# 8-Bit_Adder.net
KiCad netlist of a schematic drawn in EAGLE
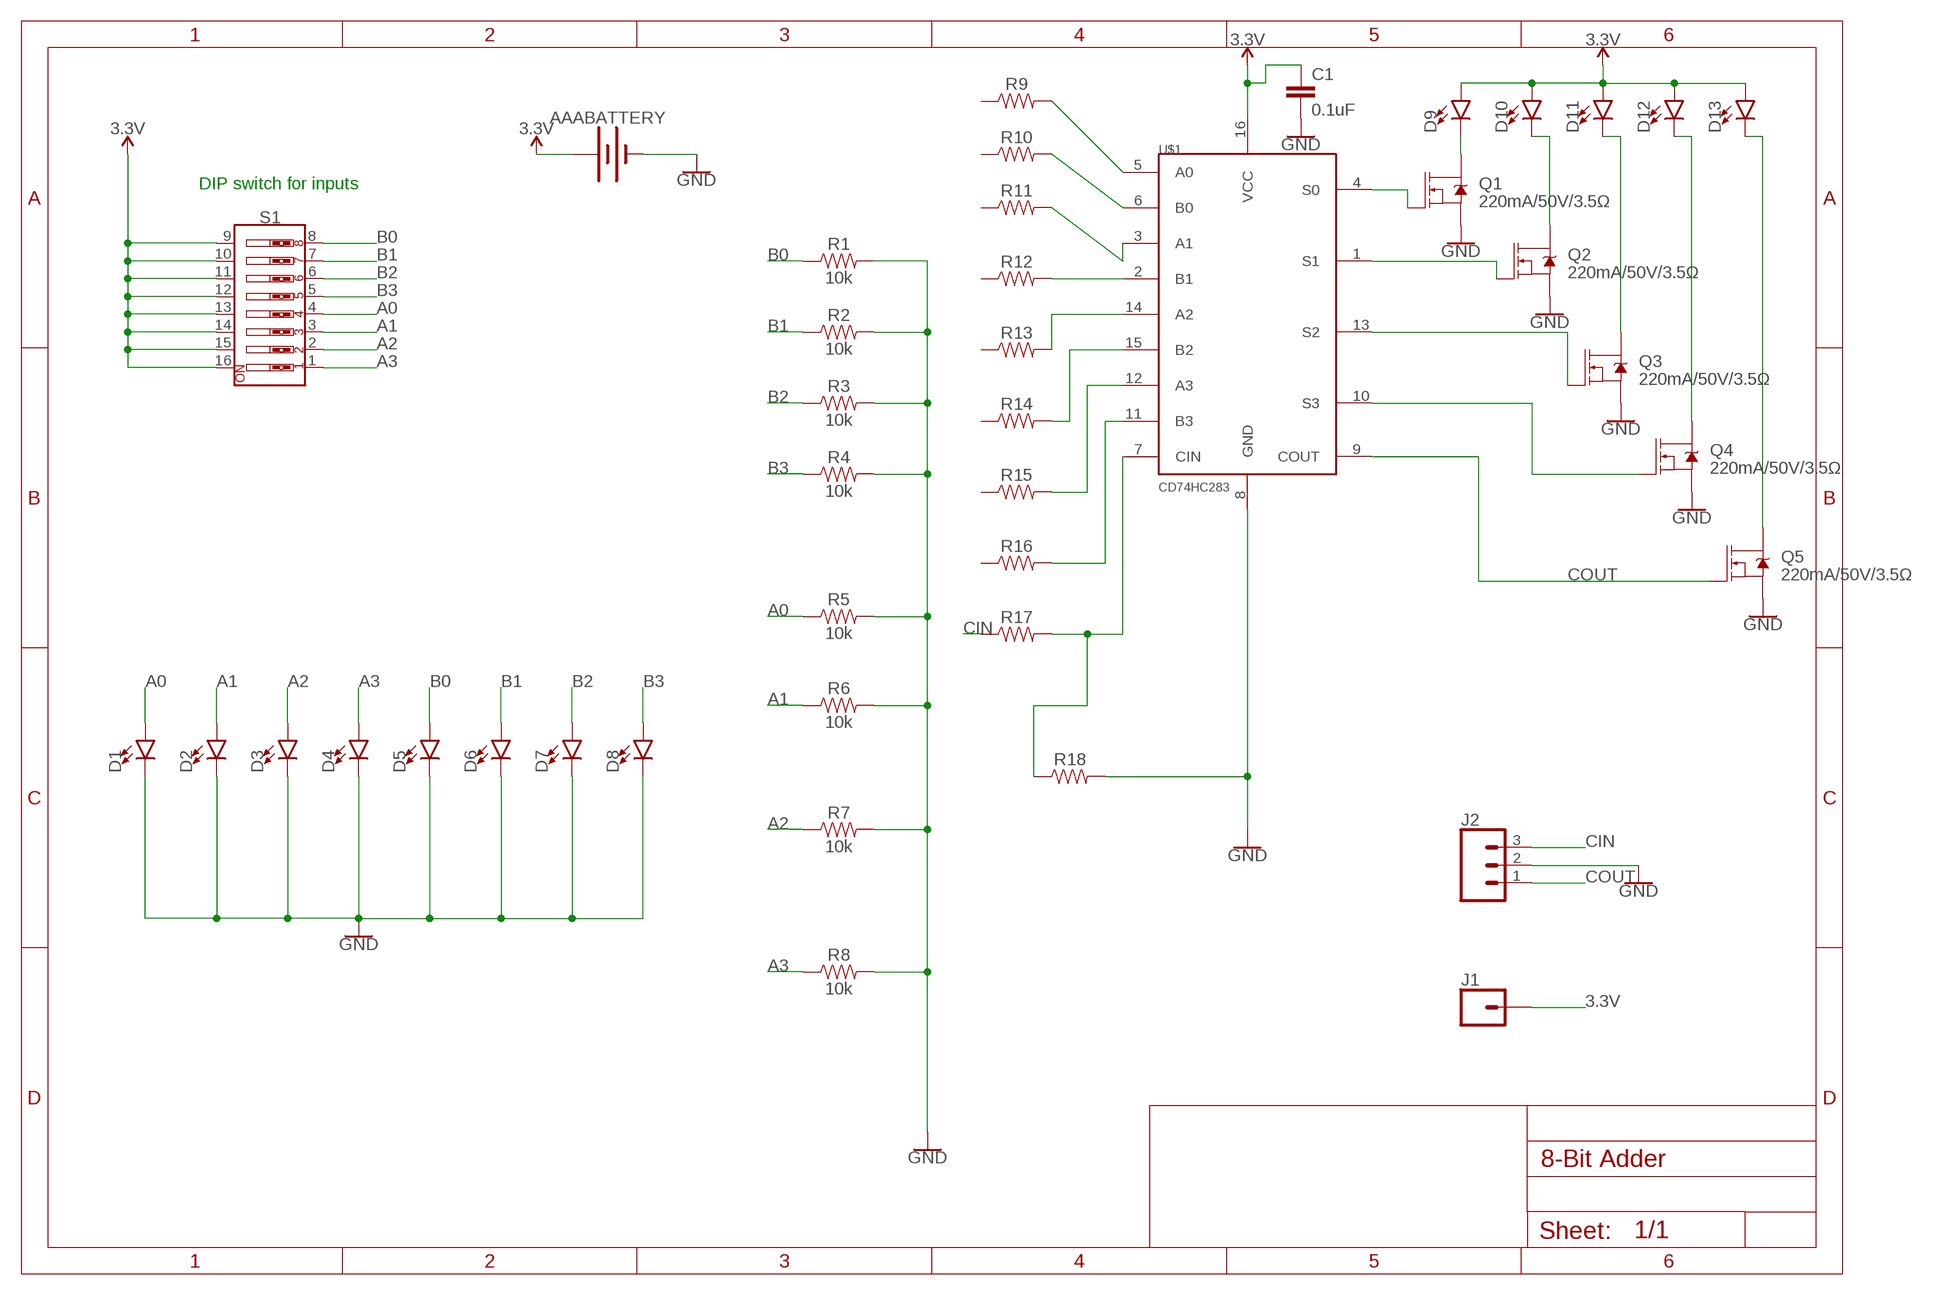
[diagram p0: schematic, sheet 1]

(export (version "E")
  (design (tool "Eeschema 10.0.6"))
  (components
    (comp (ref "AAABATTERY")
      (value "BATTERY-AAA")
      (footprint "eagle-import:BATTERY-AAA")
      (libsource (lib "eagle-import") (part "BATTERY-AAA"))
    )
    (comp (ref "C1")
      (value "0.1uF")
      (footprint "eagle-import:0603")
      (libsource (lib "eagle-import") (part "0.1UF-0603-25V-(+80/-20%)"))
    )
    (comp (ref "D1")
      (value "LED5MM")
      (footprint "eagle-import:LED_5MM")
      (libsource (lib "eagle-import") (part "LED5MM"))
    )
    (comp (ref "D2")
      (value "LED5MM")
      (footprint "eagle-import:LED_5MM")
      (libsource (lib "eagle-import") (part "LED5MM"))
    )
    (comp (ref "D3")
      (value "LED5MM")
      (footprint "eagle-import:LED_5MM")
      (libsource (lib "eagle-import") (part "LED5MM"))
    )
    (comp (ref "D4")
      (value "LED5MM")
      (footprint "eagle-import:LED_5MM")
      (libsource (lib "eagle-import") (part "LED5MM"))
    )
    (comp (ref "D5")
      (value "LED5MM")
      (footprint "eagle-import:LED_5MM")
      (libsource (lib "eagle-import") (part "LED5MM"))
    )
    (comp (ref "D6")
      (value "LED5MM")
      (footprint "eagle-import:LED_5MM")
      (libsource (lib "eagle-import") (part "LED5MM"))
    )
    (comp (ref "D7")
      (value "LED5MM")
      (footprint "eagle-import:LED_5MM")
      (libsource (lib "eagle-import") (part "LED5MM"))
    )
    (comp (ref "D8")
      (value "LED5MM")
      (footprint "eagle-import:LED_5MM")
      (libsource (lib "eagle-import") (part "LED5MM"))
    )
    (comp (ref "D9")
      (value "LED5MM")
      (footprint "eagle-import:LED_5MM")
      (libsource (lib "eagle-import") (part "LED5MM"))
    )
    (comp (ref "D10")
      (value "LED5MM")
      (footprint "eagle-import:LED_5MM")
      (libsource (lib "eagle-import") (part "LED5MM"))
    )
    (comp (ref "D11")
      (value "LED5MM")
      (footprint "eagle-import:LED_5MM")
      (libsource (lib "eagle-import") (part "LED5MM"))
    )
    (comp (ref "D12")
      (value "LED5MM")
      (footprint "eagle-import:LED_5MM")
      (libsource (lib "eagle-import") (part "LED5MM"))
    )
    (comp (ref "D13")
      (value "LED5MM")
      (footprint "eagle-import:LED_5MM")
      (libsource (lib "eagle-import") (part "LED5MM"))
    )
    (comp (ref "J1")
      (value "CONN_01")
      (footprint "eagle-import:1X01")
      (libsource (lib "eagle-import") (part "CONN_01"))
    )
    (comp (ref "J2")
      (value "CONN_03")
      (footprint "eagle-import:1X03")
      (libsource (lib "eagle-import") (part "CONN_03"))
    )
    (comp (ref "Q1")
      (value "220mA/50V/3.5Ω")
      (footprint "eagle-import:SOT23-3")
      (libsource (lib "eagle-import") (part "MOSFET-NCH-BSS138"))
    )
    (comp (ref "Q2")
      (value "220mA/50V/3.5Ω")
      (footprint "eagle-import:SOT23-3")
      (libsource (lib "eagle-import") (part "MOSFET-NCH-BSS138"))
    )
    (comp (ref "Q3")
      (value "220mA/50V/3.5Ω")
      (footprint "eagle-import:SOT23-3")
      (libsource (lib "eagle-import") (part "MOSFET-NCH-BSS138"))
    )
    (comp (ref "Q4")
      (value "220mA/50V/3.5Ω")
      (footprint "eagle-import:SOT23-3")
      (libsource (lib "eagle-import") (part "MOSFET-NCH-BSS138"))
    )
    (comp (ref "Q5")
      (value "220mA/50V/3.5Ω")
      (footprint "eagle-import:SOT23-3")
      (libsource (lib "eagle-import") (part "MOSFET-NCH-BSS138"))
    )
    (comp (ref "R1")
      (value "10k")
      (footprint "eagle-import:0603")
      (libsource (lib "eagle-import") (part "RESISTOR0603"))
    )
    (comp (ref "R2")
      (value "10k")
      (footprint "eagle-import:0603")
      (libsource (lib "eagle-import") (part "RESISTOR0603"))
    )
    (comp (ref "R3")
      (value "10k")
      (footprint "eagle-import:0603")
      (libsource (lib "eagle-import") (part "RESISTOR0603"))
    )
    (comp (ref "R4")
      (value "10k")
      (footprint "eagle-import:0603")
      (libsource (lib "eagle-import") (part "RESISTOR0603"))
    )
    (comp (ref "R5")
      (value "10k")
      (footprint "eagle-import:0603")
      (libsource (lib "eagle-import") (part "RESISTOR0603"))
    )
    (comp (ref "R6")
      (value "10k")
      (footprint "eagle-import:0603")
      (libsource (lib "eagle-import") (part "RESISTOR0603"))
    )
    (comp (ref "R7")
      (value "10k")
      (footprint "eagle-import:0603")
      (libsource (lib "eagle-import") (part "RESISTOR0603"))
    )
    (comp (ref "R8")
      (value "10k")
      (footprint "eagle-import:0603")
      (libsource (lib "eagle-import") (part "RESISTOR0603"))
    )
    (comp (ref "R9")
      (value "RESISTOR0603")
      (footprint "eagle-import:0603")
      (libsource (lib "eagle-import") (part "RESISTOR0603"))
    )
    (comp (ref "R10")
      (value "RESISTOR0603")
      (footprint "eagle-import:0603")
      (libsource (lib "eagle-import") (part "RESISTOR0603"))
    )
    (comp (ref "R11")
      (value "RESISTOR0603")
      (footprint "eagle-import:0603")
      (libsource (lib "eagle-import") (part "RESISTOR0603"))
    )
    (comp (ref "R12")
      (value "RESISTOR0603")
      (footprint "eagle-import:0603")
      (libsource (lib "eagle-import") (part "RESISTOR0603"))
    )
    (comp (ref "R13")
      (value "RESISTOR0603")
      (footprint "eagle-import:0603")
      (libsource (lib "eagle-import") (part "RESISTOR0603"))
    )
    (comp (ref "R14")
      (value "RESISTOR0603")
      (footprint "eagle-import:0603")
      (libsource (lib "eagle-import") (part "RESISTOR0603"))
    )
    (comp (ref "R15")
      (value "RESISTOR0603")
      (footprint "eagle-import:0603")
      (libsource (lib "eagle-import") (part "RESISTOR0603"))
    )
    (comp (ref "R16")
      (value "RESISTOR0603")
      (footprint "eagle-import:0603")
      (libsource (lib "eagle-import") (part "RESISTOR0603"))
    )
    (comp (ref "R17")
      (value "RESISTOR0603")
      (footprint "eagle-import:0603")
      (libsource (lib "eagle-import") (part "RESISTOR0603"))
    )
    (comp (ref "R18")
      (value "RESISTOR0603")
      (footprint "eagle-import:0603")
      (libsource (lib "eagle-import") (part "RESISTOR0603"))
    )
    (comp (ref "S1")
      (value "DIP-08-PTH")
      (footprint "eagle-import:DIPSWITCH-08")
      (libsource (lib "eagle-import") (part "DIP-08-PTH"))
    )
    (comp (ref "U$1")
      (value "CD74HC283")
      (footprint "eagle-import:SO016")
      (libsource (lib "eagle-import") (part "CD74HC283"))
    )
  )
  (nets
    (net (code "1") (name "/A0") (class "Default")
      (node (ref "D1") (pin "A") (pinfunction "A_A") (pintype "passive"))
      (node (ref "R5") (pin "1") (pinfunction "1_1") (pintype "passive"))
      (node (ref "S1") (pin "4") (pinfunction "4_4") (pintype "passive"))
    )
    (net (code "2") (name "/A1") (class "Default")
      (node (ref "D2") (pin "A") (pinfunction "A_A") (pintype "passive"))
      (node (ref "R6") (pin "1") (pinfunction "1_1") (pintype "passive"))
      (node (ref "S1") (pin "3") (pinfunction "3_3") (pintype "passive"))
    )
    (net (code "3") (name "/A2") (class "Default")
      (node (ref "D3") (pin "A") (pinfunction "A_A") (pintype "passive"))
      (node (ref "R7") (pin "1") (pinfunction "1_1") (pintype "passive"))
      (node (ref "S1") (pin "2") (pinfunction "2_2") (pintype "passive"))
    )
    (net (code "4") (name "/A3") (class "Default")
      (node (ref "D4") (pin "A") (pinfunction "A_A") (pintype "passive"))
      (node (ref "R8") (pin "1") (pinfunction "1_1") (pintype "passive"))
      (node (ref "S1") (pin "1") (pinfunction "1_1") (pintype "passive"))
    )
    (net (code "5") (name "/B0") (class "Default")
      (node (ref "D5") (pin "A") (pinfunction "A_A") (pintype "passive"))
      (node (ref "R1") (pin "1") (pinfunction "1_1") (pintype "passive"))
      (node (ref "S1") (pin "8") (pinfunction "8_8") (pintype "passive"))
    )
    (net (code "6") (name "/B1") (class "Default")
      (node (ref "D6") (pin "A") (pinfunction "A_A") (pintype "passive"))
      (node (ref "R2") (pin "1") (pinfunction "1_1") (pintype "passive"))
      (node (ref "S1") (pin "7") (pinfunction "7_7") (pintype "passive"))
    )
    (net (code "7") (name "/B2") (class "Default")
      (node (ref "D7") (pin "A") (pinfunction "A_A") (pintype "passive"))
      (node (ref "R3") (pin "1") (pinfunction "1_1") (pintype "passive"))
      (node (ref "S1") (pin "6") (pinfunction "6_6") (pintype "passive"))
    )
    (net (code "8") (name "/B3") (class "Default")
      (node (ref "D8") (pin "A") (pinfunction "A_A") (pintype "passive"))
      (node (ref "R4") (pin "1") (pinfunction "1_1") (pintype "passive"))
      (node (ref "S1") (pin "5") (pinfunction "5_5") (pintype "passive"))
    )
    (net (code "9") (name "/CIN") (class "Default")
      (node (ref "J2") (pin "3") (pinfunction "3_3") (pintype "passive"))
      (node (ref "R17") (pin "1") (pinfunction "1_1") (pintype "passive"))
    )
    (net (code "10") (name "/COUT") (class "Default")
      (node (ref "J2") (pin "1") (pinfunction "1_1") (pintype "passive"))
      (node (ref "Q5") (pin "1") (pinfunction "G_1") (pintype "bidirectional"))
      (node (ref "U$1") (pin "9") (pinfunction "COUT_9") (pintype "bidirectional"))
    )
    (net (code "11") (name "3.3V") (class "Default")
      (node (ref "AAABATTERY") (pin "PWR@1") (pinfunction "+_PWR@1") (pintype "power_in"))
      (node (ref "C1") (pin "1") (pinfunction "1_1") (pintype "passive"))
      (node (ref "D10") (pin "A") (pinfunction "A_A") (pintype "passive"))
      (node (ref "D11") (pin "A") (pinfunction "A_A") (pintype "passive"))
      (node (ref "D12") (pin "A") (pinfunction "A_A") (pintype "passive"))
      (node (ref "D13") (pin "A") (pinfunction "A_A") (pintype "passive"))
      (node (ref "D9") (pin "A") (pinfunction "A_A") (pintype "passive"))
      (node (ref "J1") (pin "1") (pinfunction "1_1") (pintype "passive"))
      (node (ref "S1") (pin "10") (pinfunction "10_10") (pintype "passive"))
      (node (ref "S1") (pin "11") (pinfunction "11_11") (pintype "passive"))
      (node (ref "S1") (pin "12") (pinfunction "12_12") (pintype "passive"))
      (node (ref "S1") (pin "13") (pinfunction "13_13") (pintype "passive"))
      (node (ref "S1") (pin "14") (pinfunction "14_14") (pintype "passive"))
      (node (ref "S1") (pin "15") (pinfunction "15_15") (pintype "passive"))
      (node (ref "S1") (pin "16") (pinfunction "16_16") (pintype "passive"))
      (node (ref "S1") (pin "9") (pinfunction "9_9") (pintype "passive"))
      (node (ref "U$1") (pin "16") (pinfunction "VCC_16") (pintype "bidirectional"))
    )
    (net (code "12") (name "GND") (class "Default")
      (node (ref "AAABATTERY") (pin "GND@1") (pinfunction "-_GND@1") (pintype "power_in"))
      (node (ref "C1") (pin "2") (pinfunction "2_2") (pintype "passive"))
      (node (ref "D1") (pin "K") (pinfunction "C_K") (pintype "passive"))
      (node (ref "D2") (pin "K") (pinfunction "C_K") (pintype "passive"))
      (node (ref "D3") (pin "K") (pinfunction "C_K") (pintype "passive"))
      (node (ref "D4") (pin "K") (pinfunction "C_K") (pintype "passive"))
      (node (ref "D5") (pin "K") (pinfunction "C_K") (pintype "passive"))
      (node (ref "D6") (pin "K") (pinfunction "C_K") (pintype "passive"))
      (node (ref "D7") (pin "K") (pinfunction "C_K") (pintype "passive"))
      (node (ref "D8") (pin "K") (pinfunction "C_K") (pintype "passive"))
      (node (ref "J2") (pin "2") (pinfunction "2_2") (pintype "passive"))
      (node (ref "Q1") (pin "2") (pinfunction "S_2") (pintype "bidirectional"))
      (node (ref "Q2") (pin "2") (pinfunction "S_2") (pintype "bidirectional"))
      (node (ref "Q3") (pin "2") (pinfunction "S_2") (pintype "bidirectional"))
      (node (ref "Q4") (pin "2") (pinfunction "S_2") (pintype "bidirectional"))
      (node (ref "Q5") (pin "2") (pinfunction "S_2") (pintype "bidirectional"))
      (node (ref "R1") (pin "2") (pinfunction "2_2") (pintype "passive"))
      (node (ref "R18") (pin "2") (pinfunction "2_2") (pintype "passive"))
      (node (ref "R2") (pin "2") (pinfunction "2_2") (pintype "passive"))
      (node (ref "R3") (pin "2") (pinfunction "2_2") (pintype "passive"))
      (node (ref "R4") (pin "2") (pinfunction "2_2") (pintype "passive"))
      (node (ref "R5") (pin "2") (pinfunction "2_2") (pintype "passive"))
      (node (ref "R6") (pin "2") (pinfunction "2_2") (pintype "passive"))
      (node (ref "R7") (pin "2") (pinfunction "2_2") (pintype "passive"))
      (node (ref "R8") (pin "2") (pinfunction "2_2") (pintype "passive"))
      (node (ref "U$1") (pin "8") (pinfunction "GND_8") (pintype "bidirectional"))
    )
    (net (code "13") (name "Net-(D9-C)") (class "Default")
      (node (ref "D9") (pin "K") (pinfunction "C_K") (pintype "passive"))
      (node (ref "Q1") (pin "3") (pinfunction "D_3") (pintype "bidirectional"))
    )
    (net (code "14") (name "Net-(D10-C)") (class "Default")
      (node (ref "D10") (pin "K") (pinfunction "C_K") (pintype "passive"))
      (node (ref "Q2") (pin "3") (pinfunction "D_3") (pintype "bidirectional"))
    )
    (net (code "15") (name "Net-(D11-C)") (class "Default")
      (node (ref "D11") (pin "K") (pinfunction "C_K") (pintype "passive"))
      (node (ref "Q3") (pin "3") (pinfunction "D_3") (pintype "bidirectional"))
    )
    (net (code "16") (name "Net-(D12-C)") (class "Default")
      (node (ref "D12") (pin "K") (pinfunction "C_K") (pintype "passive"))
      (node (ref "Q4") (pin "3") (pinfunction "D_3") (pintype "bidirectional"))
    )
    (net (code "17") (name "Net-(D13-C)") (class "Default")
      (node (ref "D13") (pin "K") (pinfunction "C_K") (pintype "passive"))
      (node (ref "Q5") (pin "3") (pinfunction "D_3") (pintype "bidirectional"))
    )
    (net (code "18") (name "Net-(Q1-G)") (class "Default")
      (node (ref "Q1") (pin "1") (pinfunction "G_1") (pintype "bidirectional"))
      (node (ref "U$1") (pin "4") (pinfunction "S0_4") (pintype "bidirectional"))
    )
    (net (code "19") (name "Net-(Q2-G)") (class "Default")
      (node (ref "Q2") (pin "1") (pinfunction "G_1") (pintype "bidirectional"))
      (node (ref "U$1") (pin "1") (pinfunction "S1_1") (pintype "bidirectional"))
    )
    (net (code "20") (name "Net-(Q3-G)") (class "Default")
      (node (ref "Q3") (pin "1") (pinfunction "G_1") (pintype "bidirectional"))
      (node (ref "U$1") (pin "13") (pinfunction "S2_13") (pintype "bidirectional"))
    )
    (net (code "21") (name "Net-(Q4-G)") (class "Default")
      (node (ref "Q4") (pin "1") (pinfunction "G_1") (pintype "bidirectional"))
      (node (ref "U$1") (pin "10") (pinfunction "S3_10") (pintype "bidirectional"))
    )
    (net (code "22") (name "Net-(U$1-A0)") (class "Default")
      (node (ref "R9") (pin "2") (pinfunction "2_2") (pintype "passive"))
      (node (ref "U$1") (pin "5") (pinfunction "A0_5") (pintype "bidirectional"))
    )
    (net (code "23") (name "Net-(U$1-A1)") (class "Default")
      (node (ref "R11") (pin "2") (pinfunction "2_2") (pintype "passive"))
      (node (ref "U$1") (pin "3") (pinfunction "A1_3") (pintype "bidirectional"))
    )
    (net (code "24") (name "Net-(U$1-A2)") (class "Default")
      (node (ref "R13") (pin "2") (pinfunction "2_2") (pintype "passive"))
      (node (ref "U$1") (pin "14") (pinfunction "A2_14") (pintype "bidirectional"))
    )
    (net (code "25") (name "Net-(U$1-A3)") (class "Default")
      (node (ref "R15") (pin "2") (pinfunction "2_2") (pintype "passive"))
      (node (ref "U$1") (pin "12") (pinfunction "A3_12") (pintype "bidirectional"))
    )
    (net (code "26") (name "Net-(U$1-B0)") (class "Default")
      (node (ref "R10") (pin "2") (pinfunction "2_2") (pintype "passive"))
      (node (ref "U$1") (pin "6") (pinfunction "B0_6") (pintype "bidirectional"))
    )
    (net (code "27") (name "Net-(U$1-B1)") (class "Default")
      (node (ref "R12") (pin "2") (pinfunction "2_2") (pintype "passive"))
      (node (ref "U$1") (pin "2") (pinfunction "B1_2") (pintype "bidirectional"))
    )
    (net (code "28") (name "Net-(U$1-B2)") (class "Default")
      (node (ref "R14") (pin "2") (pinfunction "2_2") (pintype "passive"))
      (node (ref "U$1") (pin "15") (pinfunction "B2_15") (pintype "bidirectional"))
    )
    (net (code "29") (name "Net-(U$1-B3)") (class "Default")
      (node (ref "R16") (pin "2") (pinfunction "2_2") (pintype "passive"))
      (node (ref "U$1") (pin "11") (pinfunction "B3_11") (pintype "bidirectional"))
    )
    (net (code "30") (name "Net-(U$1-CIN)") (class "Default")
      (node (ref "R17") (pin "2") (pinfunction "2_2") (pintype "passive"))
      (node (ref "R18") (pin "1") (pinfunction "1_1") (pintype "passive"))
      (node (ref "U$1") (pin "7") (pinfunction "CIN_7") (pintype "bidirectional"))
    )
    (net (code "31") (name "unconnected-(R9-Pad1)") (class "Default")
      (node (ref "R9") (pin "1") (pinfunction "1_1") (pintype "passive"))
    )
    (net (code "32") (name "unconnected-(R10-Pad1)") (class "Default")
      (node (ref "R10") (pin "1") (pinfunction "1_1") (pintype "passive"))
    )
    (net (code "33") (name "unconnected-(R11-Pad1)") (class "Default")
      (node (ref "R11") (pin "1") (pinfunction "1_1") (pintype "passive"))
    )
    (net (code "34") (name "unconnected-(R12-Pad1)") (class "Default")
      (node (ref "R12") (pin "1") (pinfunction "1_1") (pintype "passive"))
    )
    (net (code "35") (name "unconnected-(R13-Pad1)") (class "Default")
      (node (ref "R13") (pin "1") (pinfunction "1_1") (pintype "passive"))
    )
    (net (code "36") (name "unconnected-(R14-Pad1)") (class "Default")
      (node (ref "R14") (pin "1") (pinfunction "1_1") (pintype "passive"))
    )
    (net (code "37") (name "unconnected-(R15-Pad1)") (class "Default")
      (node (ref "R15") (pin "1") (pinfunction "1_1") (pintype "passive"))
    )
    (net (code "38") (name "unconnected-(R16-Pad1)") (class "Default")
      (node (ref "R16") (pin "1") (pinfunction "1_1") (pintype "passive"))
    )
  )
)
